# STM32F7.net
KiCad netlist of a schematic drawn in Altium Designer
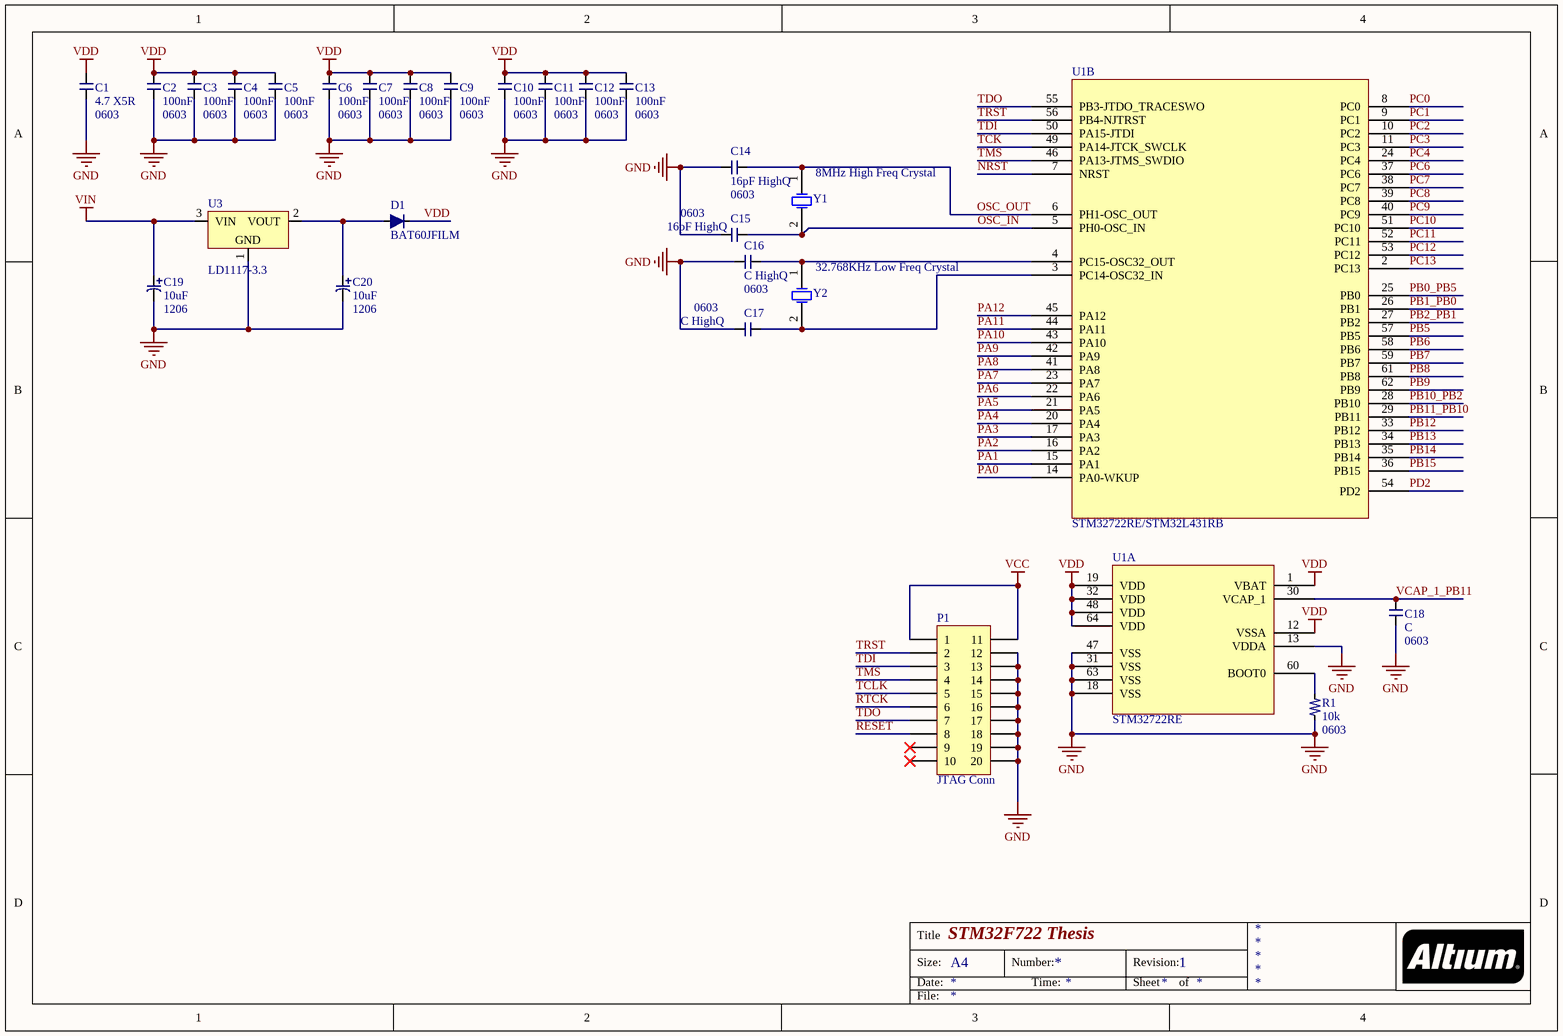
[diagram p0: STM32F7.SchDoc]

(export (version "E")
  (design (tool "Eeschema 10.0.6"))
  (components
    (comp (ref "C1")
      (value "4.7 X5R")
      (footprint "Chip 0603C")
      (fields (field (name "ALTIUM_UNNAMED_1") "0603"))
      (libsource (lib "Schlib") (part "0603-C"))
    )
    (comp (ref "C2")
      (value "100nF")
      (footprint "Chip 0603C")
      (fields (field (name "ALTIUM_UNNAMED_1") "0603"))
      (libsource (lib "Schlib") (part "0603-C"))
    )
    (comp (ref "C3")
      (value "100nF")
      (footprint "Chip 0603C")
      (fields (field (name "ALTIUM_UNNAMED_1") "0603"))
      (libsource (lib "Schlib") (part "0603-C"))
    )
    (comp (ref "C4")
      (value "100nF")
      (footprint "Chip 0603C")
      (fields (field (name "ALTIUM_UNNAMED_1") "0603"))
      (libsource (lib "Schlib") (part "0603-C"))
    )
    (comp (ref "C5")
      (value "100nF")
      (footprint "Chip 0603C")
      (fields (field (name "ALTIUM_UNNAMED_1") "0603"))
      (libsource (lib "Schlib") (part "0603-C"))
    )
    (comp (ref "C6")
      (value "100nF")
      (footprint "Chip 0603C")
      (fields (field (name "ALTIUM_UNNAMED_1") "0603"))
      (libsource (lib "Schlib") (part "0603-C"))
    )
    (comp (ref "C7")
      (value "100nF")
      (footprint "Chip 0603C")
      (fields (field (name "ALTIUM_UNNAMED_1") "0603"))
      (libsource (lib "Schlib") (part "0603-C"))
    )
    (comp (ref "C8")
      (value "100nF")
      (footprint "Chip 0603C")
      (fields (field (name "ALTIUM_UNNAMED_1") "0603"))
      (libsource (lib "Schlib") (part "0603-C"))
    )
    (comp (ref "C9")
      (value "100nF")
      (footprint "Chip 0603C")
      (fields (field (name "ALTIUM_UNNAMED_1") "0603"))
      (libsource (lib "Schlib") (part "0603-C"))
    )
    (comp (ref "C10")
      (value "100nF")
      (footprint "Chip 0603C")
      (fields (field (name "ALTIUM_UNNAMED_1") "0603"))
      (libsource (lib "Schlib") (part "0603-C"))
    )
    (comp (ref "C11")
      (value "100nF")
      (footprint "Chip 0603C")
      (fields (field (name "ALTIUM_UNNAMED_1") "0603"))
      (libsource (lib "Schlib") (part "0603-C"))
    )
    (comp (ref "C12")
      (value "100nF")
      (footprint "Chip 0603C")
      (fields (field (name "ALTIUM_UNNAMED_1") "0603"))
      (libsource (lib "Schlib") (part "0603-C"))
    )
    (comp (ref "C13")
      (value "100nF")
      (footprint "Chip 0603C")
      (fields (field (name "ALTIUM_UNNAMED_1") "0603"))
      (libsource (lib "Schlib") (part "0603-C"))
    )
    (comp (ref "C14")
      (value "16pF HighQ")
      (footprint "Chip 0603C")
      (fields (field (name "ALTIUM_UNNAMED_1") "0603"))
      (libsource (lib "Schlib") (part "0603-C"))
    )
    (comp (ref "C15")
      (value "16pF HighQ")
      (footprint "Chip 0603C")
      (fields (field (name "ALTIUM_UNNAMED_1") "0603"))
      (libsource (lib "Schlib") (part "0603-C"))
    )
    (comp (ref "C16")
      (value "C HighQ")
      (footprint "Chip 0603C")
      (fields (field (name "ALTIUM_UNNAMED_1") "0603"))
      (libsource (lib "Schlib") (part "0603-C"))
    )
    (comp (ref "C17")
      (value "C HighQ")
      (footprint "Chip 0603C")
      (fields (field (name "ALTIUM_UNNAMED_1") "0603"))
      (libsource (lib "Schlib") (part "0603-C"))
    )
    (comp (ref "C18")
      (value "C")
      (footprint "Chip 0603C")
      (fields (field (name "ALTIUM_UNNAMED_1") "0603"))
      (libsource (lib "Schlib") (part "0603-C"))
    )
    (comp (ref "C19")
      (value "10uF")
      (footprint "Chip Tan 1206")
      (fields (field (name "ALTIUM_UNNAMED_1") "1206"))
      (libsource (lib "CaesarLib_1.1") (part "CT1206"))
    )
    (comp (ref "C20")
      (value "10uF")
      (footprint "Chip Tan 1206")
      (fields (field (name "ALTIUM_UNNAMED_1") "1206"))
      (libsource (lib "CaesarLib_1.1") (part "CT1206"))
    )
    (comp (ref "D1")
      (value "BAT60JFILM")
      (footprint "SOD323")
      (libsource (lib "CaesarLib_1.1") (part "BAT60JFILM"))
    )
    (comp (ref "P1")
      (value "JTAG Conn")
      (footprint "HDR2X10_CEN")
      (description "Header, 10-Pin, Dual row")
      (fields (field (name "PUBLISHER") "Altium Limited"))
      (libsource (lib "Miscellaneous Connectors") (part "Header 10X2A"))
    )
    (comp (ref "R1")
      (value "10k")
      (footprint "Chip 0603R")
      (fields (field (name "ALTIUM_UNNAMED_1") "0603"))
      (libsource (lib "Schlib") (part "0603-R"))
    )
    (comp (ref "U1")
      (value "STM32722RE")
      (footprint "STM32F722RE-FP")
      (libsource (lib "CAESAR-Lib_sch") (part "STM32F722RE"))
    )
    (comp (ref "U3")
      (value "LD1117-3.3")
      (footprint "SOT-223")
      (description "Positive Fixed Voltage Regulator LDO 3.3V/1A")
      (libsource (lib "CaesarLib_1.1") (part "LD1117AS33TR"))
    )
    (comp (ref "Y1")
      (value "8MHz High Freq Crystal")
      (footprint "R38")
      (description "Crystal Oscillator")
      (fields (field (name "PUBLISHER") "Altium Limited"))
      (libsource (lib "Miscellaneous Devices") (part "XTAL"))
    )
    (comp (ref "Y2")
      (value "32.768KHz Low Freq Crystal")
      (footprint "R38")
      (description "Crystal Oscillator")
      (fields (field (name "PUBLISHER") "Altium Limited"))
      (libsource (lib "Miscellaneous Devices") (part "XTAL"))
    )
  )
  (nets
    (net (code "1") (name "/NRST") (class "Default")
      (node (ref "U1") (pin "7") (pinfunction "NRST_7") (pintype "passive"))
    )
    (net (code "2") (name "/OSC_IN") (class "Default")
      (node (ref "C15") (pin "2") (pinfunction "2_2") (pintype "passive"))
      (node (ref "U1") (pin "5") (pinfunction "PH0-OSC_IN_5") (pintype "passive"))
      (node (ref "Y1") (pin "2") (pinfunction "OSC2_2") (pintype "passive"))
    )
    (net (code "3") (name "/OSC_OUT") (class "Default")
      (node (ref "C14") (pin "2") (pinfunction "2_2") (pintype "passive"))
      (node (ref "U1") (pin "6") (pinfunction "PH1-OSC_OUT_6") (pintype "passive"))
      (node (ref "Y1") (pin "1") (pinfunction "OSC1_1") (pintype "passive"))
    )
    (net (code "4") (name "/PA0") (class "Default")
      (node (ref "U1") (pin "14") (pinfunction "PA0-WKUP_14") (pintype "passive"))
    )
    (net (code "5") (name "/PA1") (class "Default")
      (node (ref "U1") (pin "15") (pinfunction "PA1_15") (pintype "passive"))
    )
    (net (code "6") (name "/PA2") (class "Default")
      (node (ref "U1") (pin "16") (pinfunction "PA2_16") (pintype "passive"))
    )
    (net (code "7") (name "/PA3") (class "Default")
      (node (ref "U1") (pin "17") (pinfunction "PA3_17") (pintype "passive"))
    )
    (net (code "8") (name "/PA4") (class "Default")
      (node (ref "U1") (pin "20") (pinfunction "PA4_20") (pintype "passive"))
    )
    (net (code "9") (name "/PA5") (class "Default")
      (node (ref "U1") (pin "21") (pinfunction "PA5_21") (pintype "passive"))
    )
    (net (code "10") (name "/PA6") (class "Default")
      (node (ref "U1") (pin "22") (pinfunction "PA6_22") (pintype "passive"))
    )
    (net (code "11") (name "/PA7") (class "Default")
      (node (ref "U1") (pin "23") (pinfunction "PA7_23") (pintype "passive"))
    )
    (net (code "12") (name "/PA8") (class "Default")
      (node (ref "U1") (pin "41") (pinfunction "PA8_41") (pintype "passive"))
    )
    (net (code "13") (name "/PA9") (class "Default")
      (node (ref "U1") (pin "42") (pinfunction "PA9_42") (pintype "passive"))
    )
    (net (code "14") (name "/PA10") (class "Default")
      (node (ref "U1") (pin "43") (pinfunction "PA10_43") (pintype "passive"))
    )
    (net (code "15") (name "/PA11") (class "Default")
      (node (ref "U1") (pin "44") (pinfunction "PA11_44") (pintype "passive"))
    )
    (net (code "16") (name "/PA12") (class "Default")
      (node (ref "U1") (pin "45") (pinfunction "PA12_45") (pintype "passive"))
    )
    (net (code "17") (name "/PB0_PB5") (class "Default")
      (node (ref "U1") (pin "25") (pinfunction "PB0_25") (pintype "passive"))
    )
    (net (code "18") (name "/PB1_PB0") (class "Default")
      (node (ref "U1") (pin "26") (pinfunction "PB1_26") (pintype "passive"))
    )
    (net (code "19") (name "/PB2_PB1") (class "Default")
      (node (ref "U1") (pin "27") (pinfunction "PB2_27") (pintype "passive"))
    )
    (net (code "20") (name "/PB5") (class "Default")
      (node (ref "U1") (pin "57") (pinfunction "PB5_57") (pintype "passive"))
    )
    (net (code "21") (name "/PB6") (class "Default")
      (node (ref "U1") (pin "58") (pinfunction "PB6_58") (pintype "passive"))
    )
    (net (code "22") (name "/PB7") (class "Default")
      (node (ref "U1") (pin "59") (pinfunction "PB7_59") (pintype "passive"))
    )
    (net (code "23") (name "/PB8") (class "Default")
      (node (ref "U1") (pin "61") (pinfunction "PB8_61") (pintype "passive"))
    )
    (net (code "24") (name "/PB9") (class "Default")
      (node (ref "U1") (pin "62") (pinfunction "PB9_62") (pintype "passive"))
    )
    (net (code "25") (name "/PB10_PB2") (class "Default")
      (node (ref "U1") (pin "28") (pinfunction "PB10_28") (pintype "passive"))
    )
    (net (code "26") (name "/PB11_PB10") (class "Default")
      (node (ref "U1") (pin "29") (pinfunction "PB11_29") (pintype "passive"))
    )
    (net (code "27") (name "/PB12") (class "Default")
      (node (ref "U1") (pin "33") (pinfunction "PB12_33") (pintype "passive"))
    )
    (net (code "28") (name "/PB13") (class "Default")
      (node (ref "U1") (pin "34") (pinfunction "PB13_34") (pintype "passive"))
    )
    (net (code "29") (name "/PB14") (class "Default")
      (node (ref "U1") (pin "35") (pinfunction "PB14_35") (pintype "passive"))
    )
    (net (code "30") (name "/PB15") (class "Default")
      (node (ref "U1") (pin "36") (pinfunction "PB15_36") (pintype "passive"))
    )
    (net (code "31") (name "/PC0") (class "Default")
      (node (ref "U1") (pin "8") (pinfunction "PC0_8") (pintype "passive"))
    )
    (net (code "32") (name "/PC1") (class "Default")
      (node (ref "U1") (pin "9") (pinfunction "PC1_9") (pintype "passive"))
    )
    (net (code "33") (name "/PC2") (class "Default")
      (node (ref "U1") (pin "10") (pinfunction "PC2_10") (pintype "passive"))
    )
    (net (code "34") (name "/PC3") (class "Default")
      (node (ref "U1") (pin "11") (pinfunction "PC3_11") (pintype "passive"))
    )
    (net (code "35") (name "/PC4") (class "Default")
      (node (ref "U1") (pin "24") (pinfunction "PC4_24") (pintype "passive"))
    )
    (net (code "36") (name "/PC6") (class "Default")
      (node (ref "U1") (pin "37") (pinfunction "PC6_37") (pintype "passive"))
    )
    (net (code "37") (name "/PC7") (class "Default")
      (node (ref "U1") (pin "38") (pinfunction "PC7_38") (pintype "passive"))
    )
    (net (code "38") (name "/PC8") (class "Default")
      (node (ref "U1") (pin "39") (pinfunction "PC8_39") (pintype "passive"))
    )
    (net (code "39") (name "/PC9") (class "Default")
      (node (ref "U1") (pin "40") (pinfunction "PC9_40") (pintype "passive"))
    )
    (net (code "40") (name "/PC10") (class "Default")
      (node (ref "U1") (pin "51") (pinfunction "PC10_51") (pintype "passive"))
    )
    (net (code "41") (name "/PC11") (class "Default")
      (node (ref "U1") (pin "52") (pinfunction "PC11_52") (pintype "passive"))
    )
    (net (code "42") (name "/PC12") (class "Default")
      (node (ref "U1") (pin "53") (pinfunction "PC12_53") (pintype "passive"))
    )
    (net (code "43") (name "/PC13") (class "Default")
      (node (ref "U1") (pin "2") (pinfunction "PC13_2") (pintype "passive"))
    )
    (net (code "44") (name "/PD2") (class "Default")
      (node (ref "U1") (pin "54") (pinfunction "PD2_54") (pintype "passive"))
    )
    (net (code "45") (name "/RESET") (class "Default")
      (node (ref "P1") (pin "8") (pinfunction "8_8") (pintype "passive"))
    )
    (net (code "46") (name "/RTCK") (class "Default")
      (node (ref "P1") (pin "6") (pinfunction "6_6") (pintype "passive"))
    )
    (net (code "47") (name "/TCK") (class "Default")
      (node (ref "U1") (pin "49") (pinfunction "PA14-JTCK_SWCLK_49") (pintype "passive"))
    )
    (net (code "48") (name "/TCLK") (class "Default")
      (node (ref "P1") (pin "5") (pinfunction "5_5") (pintype "passive"))
    )
    (net (code "49") (name "/TDI") (class "Default")
      (node (ref "P1") (pin "3") (pinfunction "3_3") (pintype "passive"))
      (node (ref "U1") (pin "50") (pinfunction "PA15-JTDI_50") (pintype "passive"))
    )
    (net (code "50") (name "/TDO") (class "Default")
      (node (ref "P1") (pin "7") (pinfunction "7_7") (pintype "passive"))
      (node (ref "U1") (pin "55") (pinfunction "PB3-JTDO_TRACESWO_55") (pintype "passive"))
    )
    (net (code "51") (name "/TMS") (class "Default")
      (node (ref "P1") (pin "4") (pinfunction "4_4") (pintype "passive"))
      (node (ref "U1") (pin "46") (pinfunction "PA13-JTMS_SWDIO_46") (pintype "passive"))
    )
    (net (code "52") (name "/TRST") (class "Default")
      (node (ref "P1") (pin "2") (pinfunction "2_2") (pintype "passive"))
      (node (ref "U1") (pin "56") (pinfunction "PB4-NJTRST_56") (pintype "passive"))
    )
    (net (code "53") (name "/VCAP_1_PB11") (class "Default")
      (node (ref "C18") (pin "2") (pinfunction "2_2") (pintype "passive"))
      (node (ref "U1") (pin "30") (pinfunction "VCAP_1_30") (pintype "passive"))
    )
    (net (code "54") (name "GND") (class "Default")
      (node (ref "C1") (pin "1") (pinfunction "1_1") (pintype "passive"))
      (node (ref "C10") (pin "1") (pinfunction "1_1") (pintype "passive"))
      (node (ref "C11") (pin "1") (pinfunction "1_1") (pintype "passive"))
      (node (ref "C12") (pin "1") (pinfunction "1_1") (pintype "passive"))
      (node (ref "C13") (pin "1") (pinfunction "1_1") (pintype "passive"))
      (node (ref "C14") (pin "1") (pinfunction "1_1") (pintype "passive"))
      (node (ref "C15") (pin "1") (pinfunction "1_1") (pintype "passive"))
      (node (ref "C16") (pin "1") (pinfunction "1_1") (pintype "passive"))
      (node (ref "C17") (pin "1") (pinfunction "1_1") (pintype "passive"))
      (node (ref "C18") (pin "1") (pinfunction "1_1") (pintype "passive"))
      (node (ref "C19") (pin "2") (pinfunction "2_2") (pintype "passive"))
      (node (ref "C2") (pin "1") (pinfunction "1_1") (pintype "passive"))
      (node (ref "C20") (pin "2") (pinfunction "2_2") (pintype "passive"))
      (node (ref "C3") (pin "1") (pinfunction "1_1") (pintype "passive"))
      (node (ref "C4") (pin "1") (pinfunction "1_1") (pintype "passive"))
      (node (ref "C5") (pin "1") (pinfunction "1_1") (pintype "passive"))
      (node (ref "C6") (pin "1") (pinfunction "1_1") (pintype "passive"))
      (node (ref "C7") (pin "1") (pinfunction "1_1") (pintype "passive"))
      (node (ref "C8") (pin "1") (pinfunction "1_1") (pintype "passive"))
      (node (ref "C9") (pin "1") (pinfunction "1_1") (pintype "passive"))
      (node (ref "P1") (pin "12") (pinfunction "12_12") (pintype "passive"))
      (node (ref "P1") (pin "13") (pinfunction "13_13") (pintype "passive"))
      (node (ref "P1") (pin "14") (pinfunction "14_14") (pintype "passive"))
      (node (ref "P1") (pin "15") (pinfunction "15_15") (pintype "passive"))
      (node (ref "P1") (pin "16") (pinfunction "16_16") (pintype "passive"))
      (node (ref "P1") (pin "17") (pinfunction "17_17") (pintype "passive"))
      (node (ref "P1") (pin "18") (pinfunction "18_18") (pintype "passive"))
      (node (ref "P1") (pin "19") (pinfunction "19_19") (pintype "passive"))
      (node (ref "P1") (pin "20") (pinfunction "20_20") (pintype "passive"))
      (node (ref "R1") (pin "1") (pinfunction "1_1") (pintype "passive"))
      (node (ref "U1") (pin "13") (pinfunction "VDDA_13") (pintype "passive"))
      (node (ref "U1") (pin "18") (pinfunction "VSS_18") (pintype "passive"))
      (node (ref "U1") (pin "31") (pinfunction "VSS_31") (pintype "passive"))
      (node (ref "U1") (pin "47") (pinfunction "VSS_47") (pintype "passive"))
      (node (ref "U1") (pin "63") (pinfunction "VSS_63") (pintype "passive"))
      (node (ref "U3") (pin "1") (pinfunction "GND_1") (pintype "passive"))
    )
    (net (code "55") (name "Net-(U1A-BOOT0)") (class "Default")
      (node (ref "R1") (pin "2") (pinfunction "2_2") (pintype "passive"))
      (node (ref "U1") (pin "60") (pinfunction "BOOT0_60") (pintype "passive"))
    )
    (net (code "56") (name "Net-(U1B-PC14-OSC32_IN)") (class "Default")
      (node (ref "C17") (pin "2") (pinfunction "2_2") (pintype "passive"))
      (node (ref "U1") (pin "3") (pinfunction "PC14-OSC32_IN_3") (pintype "passive"))
      (node (ref "Y2") (pin "2") (pinfunction "OSC2_2") (pintype "passive"))
    )
    (net (code "57") (name "Net-(U1B-PC15-OSC32_OUT)") (class "Default")
      (node (ref "C16") (pin "2") (pinfunction "2_2") (pintype "passive"))
      (node (ref "U1") (pin "4") (pinfunction "PC15-OSC32_OUT_4") (pintype "passive"))
      (node (ref "Y2") (pin "1") (pinfunction "OSC1_1") (pintype "passive"))
    )
    (net (code "58") (name "Net-(U3-VOUT)") (class "Default")
      (node (ref "C20") (pin "1") (pinfunction "1_1") (pintype "passive"))
      (node (ref "D1") (pin "1") (pinfunction "1_1") (pintype "passive"))
      (node (ref "U3") (pin "2") (pinfunction "VOUT_2") (pintype "passive"))
    )
    (net (code "59") (name "VCC") (class "Default")
      (node (ref "P1") (pin "1") (pinfunction "1_1") (pintype "passive"))
      (node (ref "P1") (pin "11") (pinfunction "11_11") (pintype "passive"))
    )
    (net (code "60") (name "VDD") (class "Default")
      (node (ref "C1") (pin "2") (pinfunction "2_2") (pintype "passive"))
      (node (ref "C10") (pin "2") (pinfunction "2_2") (pintype "passive"))
      (node (ref "C11") (pin "2") (pinfunction "2_2") (pintype "passive"))
      (node (ref "C12") (pin "2") (pinfunction "2_2") (pintype "passive"))
      (node (ref "C13") (pin "2") (pinfunction "2_2") (pintype "passive"))
      (node (ref "C2") (pin "2") (pinfunction "2_2") (pintype "passive"))
      (node (ref "C3") (pin "2") (pinfunction "2_2") (pintype "passive"))
      (node (ref "C4") (pin "2") (pinfunction "2_2") (pintype "passive"))
      (node (ref "C5") (pin "2") (pinfunction "2_2") (pintype "passive"))
      (node (ref "C6") (pin "2") (pinfunction "2_2") (pintype "passive"))
      (node (ref "C7") (pin "2") (pinfunction "2_2") (pintype "passive"))
      (node (ref "C8") (pin "2") (pinfunction "2_2") (pintype "passive"))
      (node (ref "C9") (pin "2") (pinfunction "2_2") (pintype "passive"))
      (node (ref "D1") (pin "2") (pinfunction "2_2") (pintype "passive"))
      (node (ref "U1") (pin "1") (pinfunction "VBAT_1") (pintype "passive"))
      (node (ref "U1") (pin "12") (pinfunction "VSSA_12") (pintype "passive"))
      (node (ref "U1") (pin "19") (pinfunction "VDD_19") (pintype "passive"))
      (node (ref "U1") (pin "32") (pinfunction "VDD_32") (pintype "passive"))
      (node (ref "U1") (pin "48") (pinfunction "VDD_48") (pintype "passive"))
      (node (ref "U1") (pin "64") (pinfunction "VDD_64") (pintype "passive"))
    )
    (net (code "61") (name "VIN") (class "Default")
      (node (ref "C19") (pin "1") (pinfunction "1_1") (pintype "passive"))
      (node (ref "U3") (pin "3") (pinfunction "VIN_3") (pintype "passive"))
    )
    (net (code "62") (name "unconnected-(P1-Pad9)") (class "Default")
      (node (ref "P1") (pin "9") (pinfunction "9_9") (pintype "passive+no_connect"))
    )
    (net (code "63") (name "unconnected-(P1-Pad10)") (class "Default")
      (node (ref "P1") (pin "10") (pinfunction "10_10") (pintype "passive+no_connect"))
    )
  )
)
